# BOC_ADC_DAC.net
KiCad netlist of a schematic drawn in Altium Designer
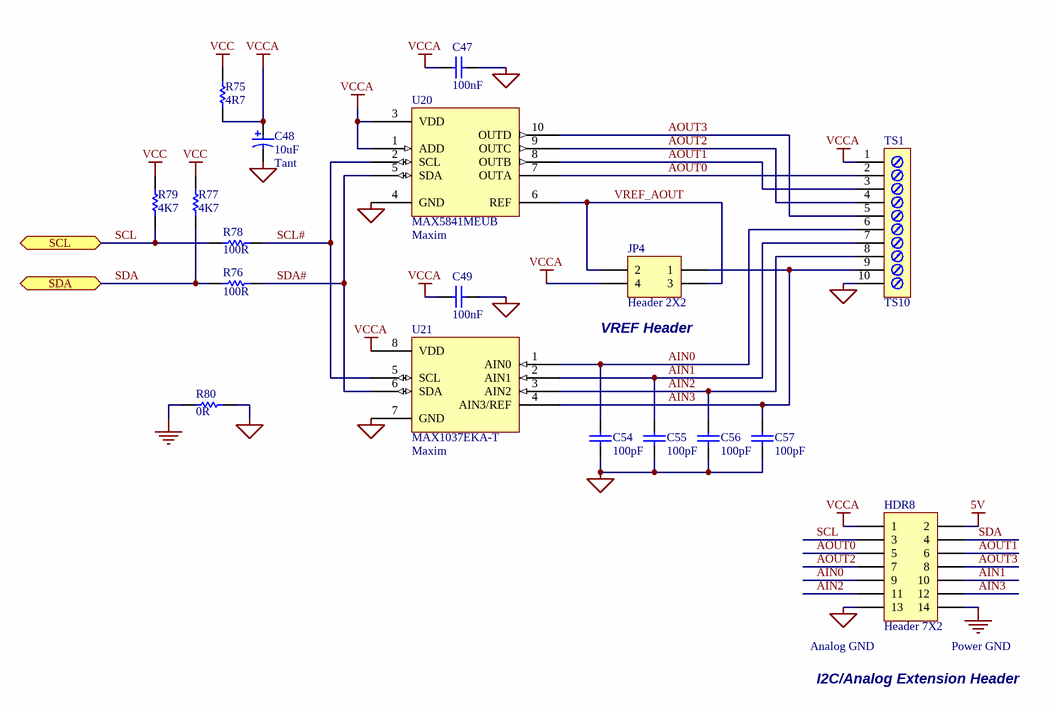
[diagram p0: BOC_ADC_DAC.SchDoc]

(export (version "E")
  (design (tool "Eeschema 10.0.6"))
  (components
    (comp (ref "C47")
      (value "100nF")
      (footprint "Altium Nanoboard Project:CC2012-0805")
      (description "Capacitor")
      (libsource (lib "Altium Nanoboard Project") (part "CAP"))
    )
    (comp (ref "C48")
      (value "10uF")
      (footprint "Altium Nanoboard Project:MCCT-B")
      (description "Polar Capacitor")
      (fields (field (name "CAPACITOR TYPE") "Tant"))
      (libsource (lib "Altium Nanoboard Project") (part "CAP_POLAR"))
    )
    (comp (ref "C49")
      (value "100nF")
      (footprint "Altium Nanoboard Project:CC2012-0805")
      (description "Capacitor")
      (libsource (lib "Altium Nanoboard Project") (part "CAP"))
    )
    (comp (ref "C54")
      (value "100pF")
      (footprint "Altium Nanoboard Project:CC2012-0805")
      (description "Capacitor")
      (libsource (lib "Altium Nanoboard Project") (part "CAP"))
    )
    (comp (ref "C55")
      (value "100pF")
      (footprint "Altium Nanoboard Project:CC2012-0805")
      (description "Capacitor")
      (libsource (lib "Altium Nanoboard Project") (part "CAP"))
    )
    (comp (ref "C56")
      (value "100pF")
      (footprint "Altium Nanoboard Project:CC2012-0805")
      (description "Capacitor")
      (libsource (lib "Altium Nanoboard Project") (part "CAP"))
    )
    (comp (ref "C57")
      (value "100pF")
      (footprint "Altium Nanoboard Project:CC2012-0805")
      (description "Capacitor")
      (libsource (lib "Altium Nanoboard Project") (part "CAP"))
    )
    (comp (ref "HDR8")
      (value "Header 7X2")
      (footprint "Altium Nanoboard Project:HDR2X7")
      (description "Header, 7-Pin, Dual row")
      (fields (field (name "MANUFACTURER") "Generic Components") (field (name "PUBLISHER") "Altium Limited"))
      (libsource (lib "Altium Nanoboard Project") (part "Header 7X2"))
    )
    (comp (ref "JP4")
      (value "Header 2X2")
      (footprint "Altium Nanoboard Project:HDR2X2_B")
      (description "Header, 2-Pin, Dual row")
      (fields (field (name "MANUFACTURER") "Generic Components") (field (name "PUBLISHER") "Altium Limited"))
      (libsource (lib "Altium Nanoboard Project") (part "Header 2X2"))
    )
    (comp (ref "R75")
      (value "4R7")
      (footprint "Altium Nanoboard Project:CC2012-0805")
      (description "Resistor")
      (libsource (lib "Altium Nanoboard Project") (part "RES"))
    )
    (comp (ref "R76")
      (value "100R")
      (footprint "Altium Nanoboard Project:CC2012-0805")
      (description "Resistor")
      (libsource (lib "Altium Nanoboard Project") (part "RES"))
    )
    (comp (ref "R77")
      (value "4K7")
      (footprint "Altium Nanoboard Project:CC2012-0805")
      (description "Resistor")
      (libsource (lib "Altium Nanoboard Project") (part "RES"))
    )
    (comp (ref "R78")
      (value "100R")
      (footprint "Altium Nanoboard Project:CC2012-0805")
      (description "Resistor")
      (libsource (lib "Altium Nanoboard Project") (part "RES"))
    )
    (comp (ref "R79")
      (value "4K7")
      (footprint "Altium Nanoboard Project:CC2012-0805")
      (description "Resistor")
      (libsource (lib "Altium Nanoboard Project") (part "RES"))
    )
    (comp (ref "R80")
      (value "0R")
      (footprint "Altium Nanoboard Project:CC2012-0805")
      (description "Resistor")
      (libsource (lib "Altium Nanoboard Project") (part "RES"))
    )
    (comp (ref "TS1")
      (value "TS10")
      (footprint "Altium Nanoboard Project:TS2.54x10")
      (description "Screw Terminal Strip, 10 Way, 2.54 mm Pitch")
      (libsource (lib "Altium Nanoboard Project") (part "TS10"))
    )
    (comp (ref "U20")
      (value "MAX5841MEUB")
      (footprint "Altium Nanoboard Project:uSOP10")
      (description "4 Channel DAC,I2C,2.7V to 5.5V")
      (fields (field (name "SUPPLIER") "Maxim"))
      (libsource (lib "Altium Nanoboard Project") (part "MAX5841"))
    )
    (comp (ref "U21")
      (value "MAX1037EKA-T")
      (footprint "Altium Nanoboard Project:SOT23_8")
      (description "4 Channel 8 Bit ADC, I2C interface, 2.7V to 3.6V Supply")
      (fields (field (name "MANUFACTURER") "Maxim"))
      (libsource (lib "Altium Nanoboard Project") (part "MAX1037"))
    )
  )
  (nets
    (net (code "1") (name "/AIN0") (class "Default")
      (node (ref "C54") (pin "1") (pinfunction "1_1") (pintype "passive"))
      (node (ref "HDR8") (pin "9") (pinfunction "9_9") (pintype "passive"))
      (node (ref "TS1") (pin "6") (pintype "passive"))
      (node (ref "U21") (pin "1") (pinfunction "AIN0_1") (pintype "input"))
    )
    (net (code "2") (name "/AIN1") (class "Default")
      (node (ref "C55") (pin "1") (pinfunction "1_1") (pintype "passive"))
      (node (ref "HDR8") (pin "10") (pinfunction "10_10") (pintype "passive"))
      (node (ref "TS1") (pin "7") (pintype "passive"))
      (node (ref "U21") (pin "2") (pinfunction "AIN1_2") (pintype "input"))
    )
    (net (code "3") (name "/AIN2") (class "Default")
      (node (ref "C56") (pin "1") (pinfunction "1_1") (pintype "passive"))
      (node (ref "HDR8") (pin "11") (pinfunction "11_11") (pintype "passive"))
      (node (ref "TS1") (pin "8") (pintype "passive"))
      (node (ref "U21") (pin "3") (pinfunction "AIN2_3") (pintype "input"))
    )
    (net (code "4") (name "/AIN3") (class "Default")
      (node (ref "C57") (pin "1") (pinfunction "1_1") (pintype "passive"))
      (node (ref "HDR8") (pin "12") (pinfunction "12_12") (pintype "passive"))
      (node (ref "JP4") (pin "1") (pinfunction "1_1") (pintype "passive"))
      (node (ref "TS1") (pin "9") (pintype "passive"))
      (node (ref "U21") (pin "4") (pinfunction "AIN3/REF_4") (pintype "power_in"))
    )
    (net (code "5") (name "/AOUT0") (class "Default")
      (node (ref "HDR8") (pin "5") (pinfunction "5_5") (pintype "passive"))
      (node (ref "TS1") (pin "2") (pintype "passive"))
      (node (ref "U20") (pin "7") (pinfunction "OUTA_7") (pintype "passive"))
    )
    (net (code "6") (name "/AOUT1") (class "Default")
      (node (ref "HDR8") (pin "6") (pinfunction "6_6") (pintype "passive"))
      (node (ref "TS1") (pin "3") (pintype "passive"))
      (node (ref "U20") (pin "8") (pinfunction "OUTB_8") (pintype "output"))
    )
    (net (code "7") (name "/AOUT2") (class "Default")
      (node (ref "HDR8") (pin "7") (pinfunction "7_7") (pintype "passive"))
      (node (ref "TS1") (pin "4") (pintype "passive"))
      (node (ref "U20") (pin "9") (pinfunction "OUTC_9") (pintype "output"))
    )
    (net (code "8") (name "/AOUT3") (class "Default")
      (node (ref "HDR8") (pin "8") (pinfunction "8_8") (pintype "passive"))
      (node (ref "TS1") (pin "5") (pintype "passive"))
      (node (ref "U20") (pin "10") (pinfunction "OUTD_10") (pintype "output"))
    )
    (net (code "9") (name "/SCL") (class "Default")
      (node (ref "HDR8") (pin "3") (pinfunction "3_3") (pintype "passive"))
      (node (ref "R78") (pin "1") (pinfunction "1_1") (pintype "passive"))
      (node (ref "R79") (pin "2") (pinfunction "2_2") (pintype "passive"))
    )
    (net (code "10") (name "/SCL#") (class "Default")
      (node (ref "R78") (pin "2") (pinfunction "2_2") (pintype "passive"))
      (node (ref "U20") (pin "2") (pinfunction "SCL_2") (pintype "bidirectional"))
      (node (ref "U21") (pin "5") (pinfunction "SCL_5") (pintype "bidirectional"))
    )
    (net (code "11") (name "/SDA") (class "Default")
      (node (ref "HDR8") (pin "4") (pinfunction "4_4") (pintype "passive"))
      (node (ref "R76") (pin "1") (pinfunction "1_1") (pintype "passive"))
      (node (ref "R77") (pin "2") (pinfunction "2_2") (pintype "passive"))
    )
    (net (code "12") (name "/SDA#") (class "Default")
      (node (ref "R76") (pin "2") (pinfunction "2_2") (pintype "passive"))
      (node (ref "U20") (pin "5") (pinfunction "SDA_5") (pintype "bidirectional"))
      (node (ref "U21") (pin "6") (pinfunction "SDA_6") (pintype "bidirectional"))
    )
    (net (code "13") (name "/VREF_AOUT") (class "Default")
      (node (ref "JP4") (pin "2") (pinfunction "2_2") (pintype "passive"))
      (node (ref "JP4") (pin "3") (pinfunction "3_3") (pintype "passive"))
      (node (ref "U20") (pin "6") (pinfunction "REF_6") (pintype "passive"))
    )
    (net (code "14") (name "5V") (class "Default")
      (node (ref "HDR8") (pin "2") (pinfunction "2_2") (pintype "passive"))
    )
    (net (code "15") (name "AGND") (class "Default")
      (node (ref "C47") (pin "2") (pinfunction "2_2") (pintype "passive"))
      (node (ref "C48") (pin "2") (pinfunction "2_2") (pintype "passive"))
      (node (ref "C49") (pin "2") (pinfunction "2_2") (pintype "passive"))
      (node (ref "C54") (pin "2") (pinfunction "2_2") (pintype "passive"))
      (node (ref "C55") (pin "2") (pinfunction "2_2") (pintype "passive"))
      (node (ref "C56") (pin "2") (pinfunction "2_2") (pintype "passive"))
      (node (ref "C57") (pin "2") (pinfunction "2_2") (pintype "passive"))
      (node (ref "HDR8") (pin "13") (pinfunction "13_13") (pintype "passive"))
      (node (ref "R80") (pin "2") (pinfunction "2_2") (pintype "passive"))
      (node (ref "TS1") (pin "10") (pintype "passive"))
      (node (ref "U20") (pin "4") (pinfunction "GND_4") (pintype "power_in"))
      (node (ref "U21") (pin "7") (pinfunction "GND_7") (pintype "power_in"))
    )
    (net (code "16") (name "GND") (class "Default")
      (node (ref "HDR8") (pin "14") (pinfunction "14_14") (pintype "passive"))
      (node (ref "R80") (pin "1") (pinfunction "1_1") (pintype "passive"))
    )
    (net (code "17") (name "VCC") (class "Default")
      (node (ref "R75") (pin "2") (pinfunction "2_2") (pintype "passive"))
      (node (ref "R77") (pin "1") (pinfunction "1_1") (pintype "passive"))
      (node (ref "R79") (pin "1") (pinfunction "1_1") (pintype "passive"))
    )
    (net (code "18") (name "VCCA") (class "Default")
      (node (ref "C47") (pin "1") (pinfunction "1_1") (pintype "passive"))
      (node (ref "C48") (pin "1") (pinfunction "1_1") (pintype "passive"))
      (node (ref "C49") (pin "1") (pinfunction "1_1") (pintype "passive"))
      (node (ref "HDR8") (pin "1") (pinfunction "1_1") (pintype "passive"))
      (node (ref "JP4") (pin "4") (pinfunction "4_4") (pintype "passive"))
      (node (ref "R75") (pin "1") (pinfunction "1_1") (pintype "passive"))
      (node (ref "TS1") (pin "1") (pintype "passive"))
      (node (ref "U20") (pin "1") (pinfunction "ADD_1") (pintype "input"))
      (node (ref "U20") (pin "3") (pinfunction "VDD_3") (pintype "power_in"))
      (node (ref "U21") (pin "8") (pinfunction "VDD_8") (pintype "power_in"))
    )
  )
)
